# AC_Power_Supply.net
KiCad netlist of a schematic drawn in Altium Designer
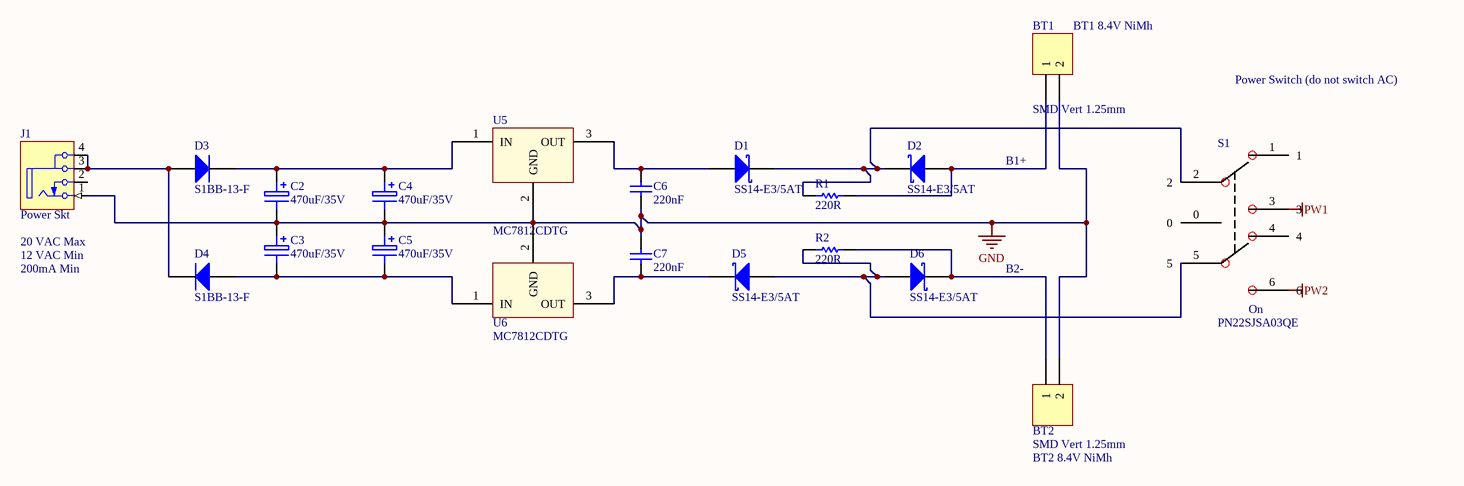
[diagram p0: AC Power Supply.SchDoc]

(export (version "E")
  (design (tool "Eeschema 10.0.6"))
  (components
    (comp (ref "BT1")
      (value "SMD Vert 1.25mm")
      (footprint "SD-53398-0219")
      (description "Header_Vert_2Pos_1.25mm_125V@1A_SMT")
      (fields
        (field (name "MANUFACTURER") "Molex Inc")
        (field (name "MANUFACTURER PART NUMBER") "0533980271")
      )
      (libsource (lib "ECE Components_16_2") (part "JB_53398-02"))
    )
    (comp (ref "BT2")
      (value "SMD Vert 1.25mm")
      (footprint "SD-53398-0219")
      (description "Header_Vert_2Pos_1.25mm_125V@1A_SMT")
      (fields
        (field (name "MANUFACTURER") "Molex Inc")
        (field (name "MANUFACTURER PART NUMBER") "0533980271")
      )
      (libsource (lib "") (part "JB_53398-02_1"))
    )
    (comp (ref "C2")
      (value "470uF/35V")
      (footprint "EEE-FK1V471SP")
      (description "CAP ALUM 470uF 35V SMD")
      (fields (field (name "MANUFACTURER") "Panasonic"))
      (libsource (lib "ECE Components_15_8") (part "CA_470uF_16V"))
    )
    (comp (ref "C3")
      (value "470uF/35V")
      (footprint "EEE-FK1V471SP")
      (description "CAP ALUM 470uF 35V SMD")
      (fields (field (name "MANUFACTURER") "Panasonic"))
      (libsource (lib "ECE Components_15_8") (part "CA_470uF_16V"))
    )
    (comp (ref "C4")
      (value "470uF/35V")
      (footprint "EEE-FK1V471SP")
      (description "CAP ALUM 470uF 35V SMD")
      (fields (field (name "MANUFACTURER") "Panasonic"))
      (libsource (lib "ECE Components_15_8") (part "CA_470uF_16V"))
    )
    (comp (ref "C5")
      (value "470uF/35V")
      (footprint "EEE-FK1V471SP")
      (description "CAP ALUM 470uF 35V SMD")
      (fields (field (name "MANUFACTURER") "Panasonic"))
      (libsource (lib "ECE Components_15_8") (part "CA_470uF_16V"))
    )
    (comp (ref "C6")
      (value "220nF")
      (footprint "CAPC1608L")
      (description "CAP CER 220nF Y5V -20% +80% 25V 0603")
      (libsource (lib "ECE Components_16_2") (part "CC_220nF_0603"))
    )
    (comp (ref "C7")
      (value "220nF")
      (footprint "CAPC1608L")
      (description "CAP CER 220nF Y5V -20% +80% 25V 0603")
      (libsource (lib "ECE Components_16_2") (part "CC_220nF_0603"))
    )
    (comp (ref "D1")
      (value "SS14-E3/5AT")
      (footprint "DIOM4227X23N")
      (description "DIODE, SCHOTTKY, 1A, 40V, DO-214AC")
      (fields
        (field (name "MANUFACTURER") "VISHAY GENERAL SEMICONDUCTOR")
        (field (name "MANUFACTURER PART NUMBER") "SS14-E3/5AT")
      )
      (libsource (lib "ECE Components_16_2") (part "DS_SS14E3"))
    )
    (comp (ref "D2")
      (value "SS14-E3/5AT")
      (footprint "DIOM4227X23N")
      (description "DIODE, SCHOTTKY, 1A, 40V, DO-214AC")
      (fields
        (field (name "MANUFACTURER") "VISHAY GENERAL SEMICONDUCTOR")
        (field (name "MANUFACTURER PART NUMBER") "SS14-E3/5AT")
      )
      (libsource (lib "ECE Components_16_2") (part "DS_SS14E3"))
    )
    (comp (ref "D3")
      (value "S1BB-13-F")
      (footprint "S1BB-13-F")
      (description "Diode Switching, Vr 75V, 200mA, SOT-416")
      (fields (field (name "MANUFACTURER") "ON Semiconductor"))
      (libsource (lib "ECE Components_15_8") (part "DR_BAS16TT1G"))
    )
    (comp (ref "D4")
      (value "S1BB-13-F")
      (footprint "S1BB-13-F")
      (description "Diode Switching, Vr 75V, 200mA, SOT-416")
      (fields (field (name "MANUFACTURER") "ON Semiconductor"))
      (libsource (lib "ECE Components_15_8") (part "DR_BAS16TT1G"))
    )
    (comp (ref "D5")
      (value "SS14-E3/5AT")
      (footprint "DIOM4227X23N")
      (description "DIODE, SCHOTTKY, 1A, 40V, DO-214AC")
      (fields
        (field (name "MANUFACTURER") "VISHAY GENERAL SEMICONDUCTOR")
        (field (name "MANUFACTURER PART NUMBER") "SS14-E3/5AT")
      )
      (libsource (lib "ECE Components_16_2") (part "DS_SS14E3"))
    )
    (comp (ref "D6")
      (value "SS14-E3/5AT")
      (footprint "DIOM4227X23N")
      (description "DIODE, SCHOTTKY, 1A, 40V, DO-214AC")
      (fields
        (field (name "MANUFACTURER") "VISHAY GENERAL SEMICONDUCTOR")
        (field (name "MANUFACTURER PART NUMBER") "SS14-E3/5AT")
      )
      (libsource (lib "ECE Components_16_2") (part "DS_SS14E3"))
    )
    (comp (ref "J1")
      (value "Power Skt")
      (footprint "1613_14")
      (description "Power supply chassis socket, SMD, Right Angle, with break contacts, 24V DC, 3.5A")
      (libsource (lib "ECE Components_16_2") (part "JP_1613 14"))
    )
    (comp (ref "R1")
      (value "220R")
      (footprint "RESC1608L")
      (description "RES 220 OHM 1/10W 5% 0603 SMD")
      (libsource (lib "ECE Components_16_2") (part "RS_220R"))
    )
    (comp (ref "R2")
      (value "220R")
      (footprint "RESC1608L")
      (description "RES 220 OHM 1/10W 5% 0603 SMD")
      (libsource (lib "ECE Components_16_2") (part "RS_220R"))
    )
    (comp (ref "S1")
      (value "PN22SJSA03QE")
      (footprint "PN22SJSA03QE - duplicate")
      (libsource (lib "Schlib1") (part "PN22SJSA03QE"))
    )
    (comp (ref "U5")
      (value "MC7812CDTG")
      (footprint "MC7812CDTRKG")
      (description "IC REG LDO 3.3V 0.3A SOT23-5")
      (fields
        (field (name "MANUFACTURER") "ON Semiconductor")
        (field (name "MANUFACTURER PART NUMBER") "MC7812CDTG")
      )
      (libsource (lib "ECE Components_16_2") (part "SV_TLV70233DBVR"))
    )
    (comp (ref "U6")
      (value "MC7812CDTG")
      (footprint "MC7812CDTRKG")
      (description "IC REG LDO 3.3V 0.3A SOT23-5")
      (fields
        (field (name "MANUFACTURER") "ON Semiconductor")
        (field (name "MANUFACTURER PART NUMBER") "MC7812CDTG")
      )
      (libsource (lib "") (part "SV_TLV70233DBVR_1"))
    )
  )
  (nets
    (net (code "1") (name "GND") (class "Default")
      (node (ref "BT1") (pin "2") (pinfunction "2_2") (pintype "passive"))
      (node (ref "BT2") (pin "2") (pinfunction "2_2") (pintype "passive"))
      (node (ref "C2") (pin "1") (pintype "passive"))
      (node (ref "C3") (pin "2") (pintype "passive"))
      (node (ref "C4") (pin "1") (pintype "passive"))
      (node (ref "C5") (pin "2") (pintype "passive"))
      (node (ref "C6") (pin "1") (pinfunction "1_1") (pintype "passive"))
      (node (ref "C7") (pin "2") (pinfunction "2_2") (pintype "passive"))
      (node (ref "J1") (pin "1") (pinfunction "T_1") (pintype "input"))
      (node (ref "U5") (pin "2") (pinfunction "GND_2") (pintype "power_in"))
      (node (ref "U6") (pin "2") (pinfunction "GND_2") (pintype "power_in"))
    )
    (net (code "2") (name "Net-(D1-A)") (class "Default")
      (node (ref "C6") (pin "2") (pinfunction "2_2") (pintype "passive"))
      (node (ref "D1") (pin "2") (pinfunction "A_2") (pintype "passive"))
      (node (ref "U5") (pin "3") (pinfunction "OUT_3") (pintype "power_in"))
    )
    (net (code "3") (name "Net-(D1-K)") (class "Default")
      (node (ref "D1") (pin "1") (pinfunction "K_1") (pintype "passive"))
      (node (ref "D2") (pin "1") (pinfunction "K_1") (pintype "passive"))
      (node (ref "R1") (pin "1") (pinfunction "1_1") (pintype "passive"))
    )
    (net (code "4") (name "Net-(D2-A)") (class "Default")
      (node (ref "BT1") (pin "1") (pinfunction "1_1") (pintype "passive"))
      (node (ref "D2") (pin "2") (pinfunction "A_2") (pintype "passive"))
      (node (ref "R1") (pin "2") (pinfunction "2_2") (pintype "passive"))
    )
    (net (code "5") (name "Net-(D3-A)") (class "Default")
      (node (ref "D3") (pin "1") (pinfunction "A_1") (pintype "passive"))
      (node (ref "D4") (pin "3") (pinfunction "K_3") (pintype "passive"))
      (node (ref "J1") (pin "3") (pinfunction "S_3") (pintype "power_in"))
      (node (ref "J1") (pin "4") (pinfunction "S_4") (pintype "power_in"))
    )
    (net (code "6") (name "Net-(D3-K)") (class "Default")
      (node (ref "C2") (pin "2") (pintype "passive"))
      (node (ref "C4") (pin "2") (pintype "passive"))
      (node (ref "D3") (pin "3") (pinfunction "K_3") (pintype "passive"))
      (node (ref "U5") (pin "1") (pinfunction "IN_1") (pintype "power_in"))
    )
    (net (code "7") (name "Net-(D4-A)") (class "Default")
      (node (ref "C3") (pin "1") (pintype "passive"))
      (node (ref "C5") (pin "1") (pintype "passive"))
      (node (ref "D4") (pin "1") (pinfunction "A_1") (pintype "passive"))
      (node (ref "U6") (pin "1") (pinfunction "IN_1") (pintype "power_in"))
    )
    (net (code "8") (name "Net-(D5-A)") (class "Default")
      (node (ref "D5") (pin "2") (pinfunction "A_2") (pintype "passive"))
      (node (ref "D6") (pin "2") (pinfunction "A_2") (pintype "passive"))
      (node (ref "R2") (pin "1") (pinfunction "1_1") (pintype "passive"))
    )
    (net (code "9") (name "Net-(D5-K)") (class "Default")
      (node (ref "C7") (pin "1") (pinfunction "1_1") (pintype "passive"))
      (node (ref "D5") (pin "1") (pinfunction "K_1") (pintype "passive"))
      (node (ref "U6") (pin "3") (pinfunction "OUT_3") (pintype "power_in"))
    )
    (net (code "10") (name "Net-(D6-K)") (class "Default")
      (node (ref "BT2") (pin "1") (pinfunction "1_1") (pintype "passive"))
      (node (ref "D6") (pin "1") (pinfunction "K_1") (pintype "passive"))
      (node (ref "R2") (pin "2") (pinfunction "2_2") (pintype "passive"))
    )
    (net (code "13") (name "unconnected-(J1-TN-Pad2)") (class "Default")
      (node (ref "J1") (pin "2") (pinfunction "TN_2") (pintype "passive"))
    )
    (net (code "14") (name "unconnected-(S1-Pad0)") (class "Default")
      (node (ref "S1") (pin "0") (pinfunction "0_0") (pintype "passive"))
    )
    (net (code "15") (name "unconnected-(S1-Pad1)") (class "Default")
      (node (ref "S1") (pin "1") (pinfunction "1_1") (pintype "passive"))
    )
    (net (code "16") (name "unconnected-(S1-Pad2)") (class "Default")
      (node (ref "S1") (pin "2") (pinfunction "2_2") (pintype "passive"))
    )
    (net (code "17") (name "unconnected-(S1-Pad3)") (class "Default")
      (node (ref "S1") (pin "3") (pinfunction "3_3") (pintype "passive"))
    )
    (net (code "18") (name "unconnected-(S1-Pad4)") (class "Default")
      (node (ref "S1") (pin "4") (pinfunction "4_4") (pintype "passive"))
    )
    (net (code "19") (name "unconnected-(S1-Pad5)") (class "Default")
      (node (ref "S1") (pin "5") (pinfunction "5_5") (pintype "passive"))
    )
    (net (code "20") (name "unconnected-(S1-Pad6)") (class "Default")
      (node (ref "S1") (pin "6") (pinfunction "6_6") (pintype "passive"))
    )
  )
)
